# midi2cv_2_2_pnl.net
KiCad netlist of a schematic drawn in EAGLE
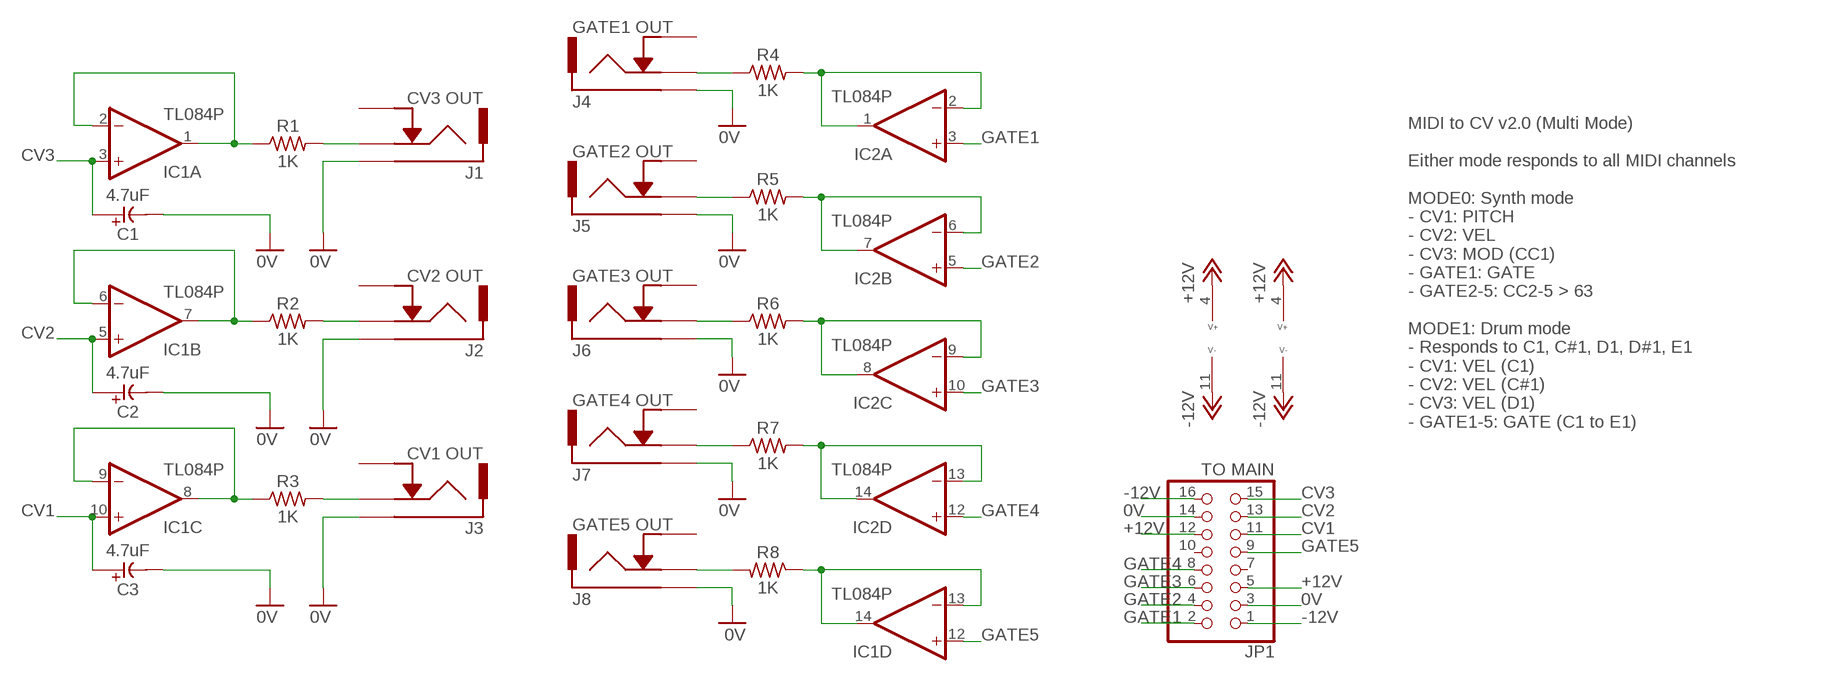
[diagram p0: schematic, sheet 1]

(export (version "E")
  (design (tool "Eeschema 10.0.6"))
  (components
    (comp (ref "C1")
      (value "4.7uF")
      (footprint "eagle-import:E2-5")
      (libsource (lib "eagle-import") (part "CE-USE2-5"))
    )
    (comp (ref "C2")
      (value "4.7uF")
      (footprint "eagle-import:E2-5")
      (libsource (lib "eagle-import") (part "CE-USE2-5"))
    )
    (comp (ref "C3")
      (value "4.7uF")
      (footprint "eagle-import:E2-5")
      (libsource (lib "eagle-import") (part "CE-USE2-5"))
    )
    (comp (ref "IC1")
      (value "TL084P")
      (footprint "eagle-import:DIL14")
      (libsource (lib "eagle-import") (part "TL084P"))
    )
    (comp (ref "IC2")
      (value "TL084P")
      (footprint "eagle-import:DIL14")
      (libsource (lib "eagle-import") (part "TL084P"))
    )
    (comp (ref "J1")
      (value "CV3 OUT")
      (footprint "eagle-import:ACJM-MV35-2S")
      (libsource (lib "eagle-import") (part "ACJM-MV35-2S"))
    )
    (comp (ref "J2")
      (value "CV2 OUT")
      (footprint "eagle-import:ACJM-MV35-2S")
      (libsource (lib "eagle-import") (part "ACJM-MV35-2S"))
    )
    (comp (ref "J3")
      (value "CV1 OUT")
      (footprint "eagle-import:ACJM-MV35-2S")
      (libsource (lib "eagle-import") (part "ACJM-MV35-2S"))
    )
    (comp (ref "J4")
      (value "GATE1 OUT")
      (footprint "eagle-import:ACJM-MV35-2S")
      (libsource (lib "eagle-import") (part "ACJM-MV35-2S"))
    )
    (comp (ref "J5")
      (value "GATE2 OUT")
      (footprint "eagle-import:ACJM-MV35-2S")
      (libsource (lib "eagle-import") (part "ACJM-MV35-2S"))
    )
    (comp (ref "J6")
      (value "GATE3 OUT")
      (footprint "eagle-import:ACJM-MV35-2S")
      (libsource (lib "eagle-import") (part "ACJM-MV35-2S"))
    )
    (comp (ref "J7")
      (value "GATE4 OUT")
      (footprint "eagle-import:ACJM-MV35-2S")
      (libsource (lib "eagle-import") (part "ACJM-MV35-2S"))
    )
    (comp (ref "J8")
      (value "GATE5 OUT")
      (footprint "eagle-import:ACJM-MV35-2S")
      (libsource (lib "eagle-import") (part "ACJM-MV35-2S"))
    )
    (comp (ref "JP1")
      (value "TO MAIN")
      (footprint "eagle-import:2X08")
      (libsource (lib "eagle-import") (part "PINHD-2X8"))
    )
    (comp (ref "R1")
      (value "1K")
      (footprint "eagle-import:0309_10")
      (libsource (lib "eagle-import") (part "R0309/10"))
    )
    (comp (ref "R2")
      (value "1K")
      (footprint "eagle-import:0309_10")
      (libsource (lib "eagle-import") (part "R0309/10"))
    )
    (comp (ref "R3")
      (value "1K")
      (footprint "eagle-import:0309_10")
      (libsource (lib "eagle-import") (part "R0309/10"))
    )
    (comp (ref "R4")
      (value "1K")
      (footprint "eagle-import:0309_10")
      (libsource (lib "eagle-import") (part "R0309/10"))
    )
    (comp (ref "R5")
      (value "1K")
      (footprint "eagle-import:0309_10")
      (libsource (lib "eagle-import") (part "R0309/10"))
    )
    (comp (ref "R6")
      (value "1K")
      (footprint "eagle-import:0309_10")
      (libsource (lib "eagle-import") (part "R0309/10"))
    )
    (comp (ref "R7")
      (value "1K")
      (footprint "eagle-import:0309_10")
      (libsource (lib "eagle-import") (part "R0309/10"))
    )
    (comp (ref "R8")
      (value "1K")
      (footprint "eagle-import:0309_10")
      (libsource (lib "eagle-import") (part "R0309/10"))
    )
  )
  (nets
    (net (code "1") (name "+12V") (class "Default")
      (node (ref "IC1") (pin "4") (pinfunction "V+_4") (pintype "power_in"))
      (node (ref "IC2") (pin "4") (pinfunction "V+_4") (pintype "power_in"))
      (node (ref "JP1") (pin "12") (pinfunction "12_12") (pintype "passive"))
      (node (ref "JP1") (pin "5") (pinfunction "5_5") (pintype "passive"))
    )
    (net (code "2") (name "-12V") (class "Default")
      (node (ref "IC1") (pin "11") (pinfunction "V-_11") (pintype "power_in"))
      (node (ref "IC2") (pin "11") (pinfunction "V-_11") (pintype "power_in"))
      (node (ref "JP1") (pin "1") (pinfunction "1_1") (pintype "passive"))
      (node (ref "JP1") (pin "16") (pinfunction "16_16") (pintype "passive"))
    )
    (net (code "3") (name "/CV1") (class "Default")
      (node (ref "C3") (pin "+") (pinfunction "+_+") (pintype "passive"))
      (node (ref "IC1") (pin "10") (pinfunction "+IN_10") (pintype "input"))
      (node (ref "JP1") (pin "11") (pinfunction "11_11") (pintype "passive"))
    )
    (net (code "4") (name "/CV2") (class "Default")
      (node (ref "C2") (pin "+") (pinfunction "+_+") (pintype "passive"))
      (node (ref "IC1") (pin "5") (pinfunction "+IN_5") (pintype "input"))
      (node (ref "JP1") (pin "13") (pinfunction "13_13") (pintype "passive"))
    )
    (net (code "5") (name "/CV3") (class "Default")
      (node (ref "C1") (pin "+") (pinfunction "+_+") (pintype "passive"))
      (node (ref "IC1") (pin "3") (pinfunction "+IN_3") (pintype "input"))
      (node (ref "JP1") (pin "15") (pinfunction "15_15") (pintype "passive"))
    )
    (net (code "6") (name "/GATE1") (class "Default")
      (node (ref "IC2") (pin "3") (pinfunction "+IN_3") (pintype "input"))
      (node (ref "JP1") (pin "2") (pinfunction "2_2") (pintype "passive"))
    )
    (net (code "7") (name "/GATE2") (class "Default")
      (node (ref "IC2") (pin "5") (pinfunction "+IN_5") (pintype "input"))
      (node (ref "JP1") (pin "4") (pinfunction "4_4") (pintype "passive"))
    )
    (net (code "8") (name "/GATE3") (class "Default")
      (node (ref "IC2") (pin "10") (pinfunction "+IN_10") (pintype "input"))
      (node (ref "JP1") (pin "6") (pinfunction "6_6") (pintype "passive"))
    )
    (net (code "9") (name "/GATE4") (class "Default")
      (node (ref "IC2") (pin "12") (pinfunction "+IN_12") (pintype "input"))
      (node (ref "JP1") (pin "8") (pinfunction "8_8") (pintype "passive"))
    )
    (net (code "10") (name "/GATE5") (class "Default")
      (node (ref "IC1") (pin "12") (pinfunction "+IN_12") (pintype "input"))
      (node (ref "JP1") (pin "9") (pinfunction "9_9") (pintype "passive"))
    )
    (net (code "11") (name "0V") (class "Default")
      (node (ref "C1") (pin "-") (pinfunction "-_-") (pintype "passive"))
      (node (ref "C2") (pin "-") (pinfunction "-_-") (pintype "passive"))
      (node (ref "C3") (pin "-") (pinfunction "-_-") (pintype "passive"))
      (node (ref "J1") (pin "P$1") (pinfunction "P$1_P$1") (pintype "bidirectional"))
      (node (ref "J2") (pin "P$1") (pinfunction "P$1_P$1") (pintype "bidirectional"))
      (node (ref "J3") (pin "P$1") (pinfunction "P$1_P$1") (pintype "bidirectional"))
      (node (ref "J4") (pin "P$1") (pinfunction "P$1_P$1") (pintype "bidirectional"))
      (node (ref "J5") (pin "P$1") (pinfunction "P$1_P$1") (pintype "bidirectional"))
      (node (ref "J6") (pin "P$1") (pinfunction "P$1_P$1") (pintype "bidirectional"))
      (node (ref "J7") (pin "P$1") (pinfunction "P$1_P$1") (pintype "bidirectional"))
      (node (ref "J8") (pin "P$1") (pinfunction "P$1_P$1") (pintype "bidirectional"))
      (node (ref "JP1") (pin "14") (pinfunction "14_14") (pintype "passive"))
      (node (ref "JP1") (pin "3") (pinfunction "3_3") (pintype "passive"))
    )
    (net (code "12") (name "Net-(IC1A--IN)") (class "Default")
      (node (ref "IC1") (pin "1") (pinfunction "OUT_1") (pintype "output"))
      (node (ref "IC1") (pin "2") (pinfunction "-IN_2") (pintype "input"))
      (node (ref "R1") (pin "1") (pinfunction "1_1") (pintype "passive"))
    )
    (net (code "13") (name "Net-(IC1B--IN)") (class "Default")
      (node (ref "IC1") (pin "6") (pinfunction "-IN_6") (pintype "input"))
      (node (ref "IC1") (pin "7") (pinfunction "OUT_7") (pintype "output"))
      (node (ref "R2") (pin "1") (pinfunction "1_1") (pintype "passive"))
    )
    (net (code "14") (name "Net-(IC1C--IN)") (class "Default")
      (node (ref "IC1") (pin "8") (pinfunction "OUT_8") (pintype "output"))
      (node (ref "IC1") (pin "9") (pinfunction "-IN_9") (pintype "input"))
      (node (ref "R3") (pin "1") (pinfunction "1_1") (pintype "passive"))
    )
    (net (code "15") (name "Net-(IC1D--IN)") (class "Default")
      (node (ref "IC1") (pin "13") (pinfunction "-IN_13") (pintype "input"))
      (node (ref "IC1") (pin "14") (pinfunction "OUT_14") (pintype "output"))
      (node (ref "R8") (pin "1") (pinfunction "1_1") (pintype "passive"))
    )
    (net (code "16") (name "Net-(IC2A--IN)") (class "Default")
      (node (ref "IC2") (pin "1") (pinfunction "OUT_1") (pintype "output"))
      (node (ref "IC2") (pin "2") (pinfunction "-IN_2") (pintype "input"))
      (node (ref "R4") (pin "2") (pinfunction "2_2") (pintype "passive"))
    )
    (net (code "17") (name "Net-(IC2B--IN)") (class "Default")
      (node (ref "IC2") (pin "6") (pinfunction "-IN_6") (pintype "input"))
      (node (ref "IC2") (pin "7") (pinfunction "OUT_7") (pintype "output"))
      (node (ref "R5") (pin "2") (pinfunction "2_2") (pintype "passive"))
    )
    (net (code "18") (name "Net-(IC2C--IN)") (class "Default")
      (node (ref "IC2") (pin "8") (pinfunction "OUT_8") (pintype "output"))
      (node (ref "IC2") (pin "9") (pinfunction "-IN_9") (pintype "input"))
      (node (ref "R6") (pin "2") (pinfunction "2_2") (pintype "passive"))
    )
    (net (code "19") (name "Net-(IC2D--IN)") (class "Default")
      (node (ref "IC2") (pin "13") (pinfunction "-IN_13") (pintype "input"))
      (node (ref "IC2") (pin "14") (pinfunction "OUT_14") (pintype "output"))
      (node (ref "R7") (pin "2") (pinfunction "2_2") (pintype "passive"))
    )
    (net (code "20") (name "Net-(J1-P$2)") (class "Default")
      (node (ref "J1") (pin "P$3") (pinfunction "P$2_P$3") (pintype "bidirectional"))
      (node (ref "R1") (pin "2") (pinfunction "2_2") (pintype "passive"))
    )
    (net (code "21") (name "Net-(J2-P$2)") (class "Default")
      (node (ref "J2") (pin "P$3") (pinfunction "P$2_P$3") (pintype "bidirectional"))
      (node (ref "R2") (pin "2") (pinfunction "2_2") (pintype "passive"))
    )
    (net (code "22") (name "Net-(J3-P$2)") (class "Default")
      (node (ref "J3") (pin "P$3") (pinfunction "P$2_P$3") (pintype "bidirectional"))
      (node (ref "R3") (pin "2") (pinfunction "2_2") (pintype "passive"))
    )
    (net (code "23") (name "Net-(J4-P$2)") (class "Default")
      (node (ref "J4") (pin "P$3") (pinfunction "P$2_P$3") (pintype "bidirectional"))
      (node (ref "R4") (pin "1") (pinfunction "1_1") (pintype "passive"))
    )
    (net (code "24") (name "Net-(J5-P$2)") (class "Default")
      (node (ref "J5") (pin "P$3") (pinfunction "P$2_P$3") (pintype "bidirectional"))
      (node (ref "R5") (pin "1") (pinfunction "1_1") (pintype "passive"))
    )
    (net (code "25") (name "Net-(J6-P$2)") (class "Default")
      (node (ref "J6") (pin "P$3") (pinfunction "P$2_P$3") (pintype "bidirectional"))
      (node (ref "R6") (pin "1") (pinfunction "1_1") (pintype "passive"))
    )
    (net (code "26") (name "Net-(J7-P$2)") (class "Default")
      (node (ref "J7") (pin "P$3") (pinfunction "P$2_P$3") (pintype "bidirectional"))
      (node (ref "R7") (pin "1") (pinfunction "1_1") (pintype "passive"))
    )
    (net (code "27") (name "Net-(J8-P$2)") (class "Default")
      (node (ref "J8") (pin "P$3") (pinfunction "P$2_P$3") (pintype "bidirectional"))
      (node (ref "R8") (pin "2") (pinfunction "2_2") (pintype "passive"))
    )
    (net (code "28") (name "unconnected-(J1-P$3-PadP$2)") (class "Default")
      (node (ref "J1") (pin "P$2") (pinfunction "P$3_P$2") (pintype "bidirectional"))
    )
    (net (code "29") (name "unconnected-(J2-P$3-PadP$2)") (class "Default")
      (node (ref "J2") (pin "P$2") (pinfunction "P$3_P$2") (pintype "bidirectional"))
    )
    (net (code "30") (name "unconnected-(J3-P$3-PadP$2)") (class "Default")
      (node (ref "J3") (pin "P$2") (pinfunction "P$3_P$2") (pintype "bidirectional"))
    )
    (net (code "31") (name "unconnected-(J4-P$3-PadP$2)") (class "Default")
      (node (ref "J4") (pin "P$2") (pinfunction "P$3_P$2") (pintype "bidirectional"))
    )
    (net (code "32") (name "unconnected-(J5-P$3-PadP$2)") (class "Default")
      (node (ref "J5") (pin "P$2") (pinfunction "P$3_P$2") (pintype "bidirectional"))
    )
    (net (code "33") (name "unconnected-(J6-P$3-PadP$2)") (class "Default")
      (node (ref "J6") (pin "P$2") (pinfunction "P$3_P$2") (pintype "bidirectional"))
    )
    (net (code "34") (name "unconnected-(J7-P$3-PadP$2)") (class "Default")
      (node (ref "J7") (pin "P$2") (pinfunction "P$3_P$2") (pintype "bidirectional"))
    )
    (net (code "35") (name "unconnected-(J8-P$3-PadP$2)") (class "Default")
      (node (ref "J8") (pin "P$2") (pinfunction "P$3_P$2") (pintype "bidirectional"))
    )
    (net (code "36") (name "unconnected-(JP1-Pad7)") (class "Default")
      (node (ref "JP1") (pin "7") (pinfunction "7_7") (pintype "passive"))
    )
    (net (code "37") (name "unconnected-(JP1-Pad10)") (class "Default")
      (node (ref "JP1") (pin "10") (pinfunction "10_10") (pintype "passive"))
    )
  )
)
